# ESP8266-Programmer_2015-11-16.net
KiCad netlist of a schematic drawn in EAGLE
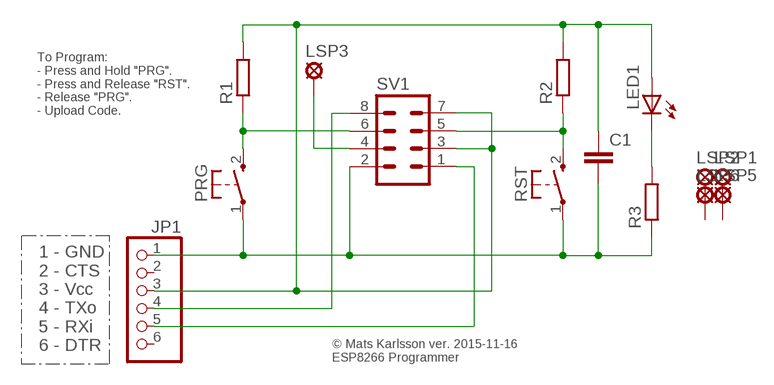
[diagram p0: schematic, sheet 1]

(export (version "E")
  (design (tool "Eeschema 10.0.6"))
  (components
    (comp (ref "C1")
      (value "C-EU025_050-035X075")
      (footprint "eagle-import:C025_050-035X075")
      (libsource (lib "eagle-import") (part "C-EU025_050-035X075"))
    )
    (comp (ref "JP1")
      (value "PINHD-1X6")
      (footprint "eagle-import:1X06")
      (libsource (lib "eagle-import") (part "PINHD-1X6"))
    )
    (comp (ref "LED1")
      (value "TLLG4400")
      (footprint "eagle-import:LED3MM")
      (fields (field (name "MF") "VISHAY SEMICONDUCTOR"))
      (libsource (lib "eagle-import") (part "TLLG4400"))
    )
    (comp (ref "LSP1")
      (value "SE11")
      (footprint "eagle-import:SE11")
      (libsource (lib "eagle-import") (part "SE11"))
    )
    (comp (ref "LSP2")
      (value "SE11")
      (footprint "eagle-import:SE11")
      (libsource (lib "eagle-import") (part "SE11"))
    )
    (comp (ref "LSP3")
      (value "SE11")
      (footprint "eagle-import:SE11")
      (libsource (lib "eagle-import") (part "SE11"))
    )
    (comp (ref "LSP5")
      (value "SE11")
      (footprint "eagle-import:SE11")
      (libsource (lib "eagle-import") (part "SE11"))
    )
    (comp (ref "LSP6")
      (value "SE11")
      (footprint "eagle-import:SE11")
      (libsource (lib "eagle-import") (part "SE11"))
    )
    (comp (ref "PRG")
      (value "KSS-2EG4430")
      (footprint "eagle-import:KSS-2EG4430")
      (libsource (lib "eagle-import") (part "KSS-2EG4430"))
    )
    (comp (ref "R1")
      (value "R-EU_0204/5")
      (footprint "eagle-import:0204_5")
      (libsource (lib "eagle-import") (part "R-EU_0204/5"))
    )
    (comp (ref "R2")
      (value "R-EU_0204/5")
      (footprint "eagle-import:0204_5")
      (libsource (lib "eagle-import") (part "R-EU_0204/5"))
    )
    (comp (ref "R3")
      (value "R-EU_0204/7")
      (footprint "eagle-import:0204_7")
      (libsource (lib "eagle-import") (part "R-EU_0204/7"))
    )
    (comp (ref "RST")
      (value "KSS-2EG4430")
      (footprint "eagle-import:KSS-2EG4430")
      (libsource (lib "eagle-import") (part "KSS-2EG4430"))
    )
    (comp (ref "SV1")
      (value "MA04-2")
      (footprint "eagle-import:MA04-2")
      (libsource (lib "eagle-import") (part "MA04-2"))
    )
  )
  (nets
    (net (code "1") (name "Net-(C1-Pad1)") (class "Default")
      (node (ref "C1") (pin "1") (pinfunction "1_1") (pintype "passive"))
      (node (ref "JP1") (pin "3") (pinfunction "3_3") (pintype "passive"))
      (node (ref "LED1") (pin "A") (pinfunction "A_A") (pintype "passive"))
      (node (ref "R1") (pin "2") (pinfunction "2_2") (pintype "passive"))
      (node (ref "R2") (pin "2") (pinfunction "2_2") (pintype "passive"))
      (node (ref "SV1") (pin "3") (pinfunction "3_3") (pintype "passive"))
      (node (ref "SV1") (pin "7") (pinfunction "7_7") (pintype "passive"))
    )
    (net (code "2") (name "Net-(JP1-Pad4)") (class "Default")
      (node (ref "JP1") (pin "4") (pinfunction "4_4") (pintype "passive"))
      (node (ref "SV1") (pin "8") (pinfunction "8_8") (pintype "passive"))
    )
    (net (code "3") (name "Net-(JP1-Pad5)") (class "Default")
      (node (ref "JP1") (pin "5") (pinfunction "5_5") (pintype "passive"))
      (node (ref "SV1") (pin "1") (pinfunction "1_1") (pintype "passive"))
    )
    (net (code "4") (name "Net-(LED1-C)") (class "Default")
      (node (ref "LED1") (pin "K") (pinfunction "C_K") (pintype "passive"))
      (node (ref "R3") (pin "2") (pinfunction "2_2") (pintype "passive"))
    )
    (net (code "5") (name "Net-(LSP3-PadMP)") (class "Default")
      (node (ref "LSP3") (pin "MP") (pinfunction "MP_MP") (pintype "passive"))
      (node (ref "SV1") (pin "4") (pinfunction "4_4") (pintype "passive"))
    )
    (net (code "6") (name "Net-(PRG-P)") (class "Default")
      (node (ref "C1") (pin "2") (pinfunction "2_2") (pintype "passive"))
      (node (ref "JP1") (pin "1") (pinfunction "1_1") (pintype "passive"))
      (node (ref "PRG") (pin "1") (pinfunction "P_1") (pintype "passive"))
      (node (ref "R3") (pin "1") (pinfunction "1_1") (pintype "passive"))
      (node (ref "RST") (pin "1") (pinfunction "P_1") (pintype "passive"))
      (node (ref "SV1") (pin "2") (pinfunction "2_2") (pintype "passive"))
    )
    (net (code "7") (name "Net-(PRG-S)") (class "Default")
      (node (ref "PRG") (pin "2") (pinfunction "S_2") (pintype "passive"))
      (node (ref "R1") (pin "1") (pinfunction "1_1") (pintype "passive"))
      (node (ref "SV1") (pin "6") (pinfunction "6_6") (pintype "passive"))
    )
    (net (code "8") (name "Net-(RST-S)") (class "Default")
      (node (ref "R2") (pin "1") (pinfunction "1_1") (pintype "passive"))
      (node (ref "RST") (pin "2") (pinfunction "S_2") (pintype "passive"))
      (node (ref "SV1") (pin "5") (pinfunction "5_5") (pintype "passive"))
    )
    (net (code "9") (name "unconnected-(JP1-Pad2)") (class "Default")
      (node (ref "JP1") (pin "2") (pinfunction "2_2") (pintype "passive"))
    )
    (net (code "10") (name "unconnected-(JP1-Pad6)") (class "Default")
      (node (ref "JP1") (pin "6") (pinfunction "6_6") (pintype "passive"))
    )
    (net (code "11") (name "unconnected-(LSP1-PadMP)") (class "Default")
      (node (ref "LSP1") (pin "MP") (pinfunction "MP_MP") (pintype "passive"))
    )
    (net (code "12") (name "unconnected-(LSP2-PadMP)") (class "Default")
      (node (ref "LSP2") (pin "MP") (pinfunction "MP_MP") (pintype "passive"))
    )
    (net (code "13") (name "unconnected-(LSP5-PadMP)") (class "Default")
      (node (ref "LSP5") (pin "MP") (pinfunction "MP_MP") (pintype "passive"))
    )
    (net (code "14") (name "unconnected-(LSP6-PadMP)") (class "Default")
      (node (ref "LSP6") (pin "MP") (pinfunction "MP_MP") (pintype "passive"))
    )
  )
)
